# Schematic_shield_Rovables_v2.net
KiCad netlist of a schematic drawn in Altium Designer
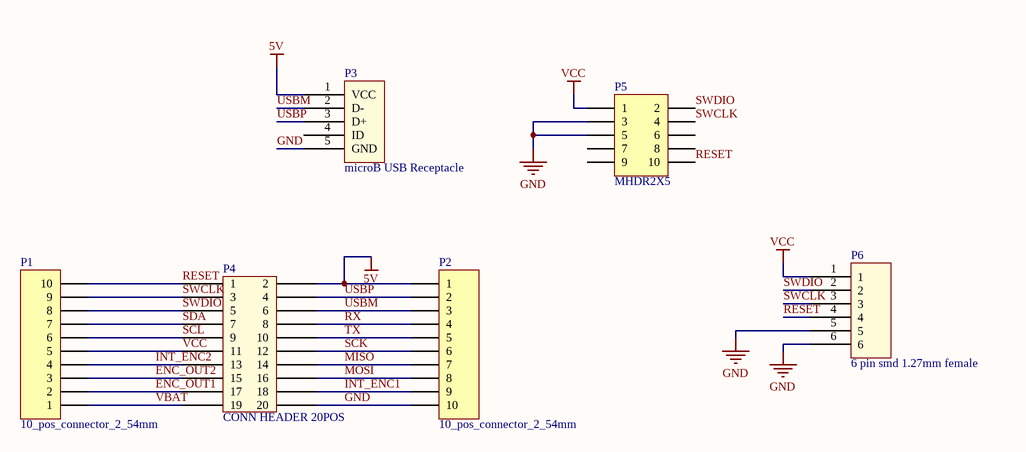
[diagram p0: Schematic_shield_Rovables_v2.SchDoc]

(export (version "E")
  (design (tool "Eeschema 10.0.6"))
  (components
    (comp (ref "P1")
      (value "10_pos_connector_2_54mm")
      (footprint "2_54mm_10_pos_connector")
      (libsource (lib "Artem_Library") (part "10_pos_connector_2_54mm"))
    )
    (comp (ref "P2")
      (value "10_pos_connector_2_54mm")
      (footprint "2_54mm_10_pos_connector")
      (libsource (lib "") (part "10_pos_connector_2_54mm_1"))
    )
    (comp (ref "P3")
      (value "microB USB Receptacle")
      (footprint "MicroB USB Standarad SMT")
      (fields (field (name "MANUFACTURER") "ZX62-B-5PA(11)"))
      (libsource (lib "Artem_Library") (part "microB USB Receptacle"))
    )
    (comp (ref "P4")
      (value "CONN HEADER 20POS")
      (footprint "DF12 20 POS")
      (fields
        (field (name "DIGIKEY PART NUMBER") "H11743CT-ND")
        (field (name "MANUFACTURER PART NUMBER") "DF12D(4.0)-20DP-0.5V(81)")
        (field (name "MANUFACTURER") "Hirose Electric Co Ltd")
      )
      (libsource (lib "Artem_Library") (part "CONN HEADER 20POS"))
    )
    (comp (ref "P5")
      (value "MHDR2X5")
      (footprint "MHDR2X5")
      (description "Header, 5-Pin, Dual row")
      (fields (field (name "PUBLISHER") "Altium Limited"))
      (libsource (lib "Miscellaneous Connectors") (part "MHDR2X5"))
    )
    (comp (ref "P6")
      (value "6 pin smd 1.27mm female")
      (footprint "6pos 1.27mm")
      (libsource (lib "Artem_Library") (part "6 pin smd 1.27mm female"))
    )
  )
  (nets
    (net (code "1") (name "/ENC_OUT1") (class "Default")
      (node (ref "P1") (pin "2") (pinfunction "2_2") (pintype "passive"))
      (node (ref "P4") (pin "17") (pinfunction "17_17") (pintype "passive"))
    )
    (net (code "2") (name "/ENC_OUT2") (class "Default")
      (node (ref "P1") (pin "3") (pinfunction "3_3") (pintype "passive"))
      (node (ref "P4") (pin "15") (pinfunction "15_15") (pintype "passive"))
    )
    (net (code "3") (name "/INT_ENC1") (class "Default")
      (node (ref "P2") (pin "9") (pinfunction "9_9") (pintype "passive"))
      (node (ref "P4") (pin "18") (pinfunction "18_18") (pintype "passive"))
    )
    (net (code "4") (name "/INT_ENC2") (class "Default")
      (node (ref "P1") (pin "4") (pinfunction "4_4") (pintype "passive"))
      (node (ref "P4") (pin "13") (pinfunction "13_13") (pintype "passive"))
    )
    (net (code "5") (name "/MISO") (class "Default")
      (node (ref "P2") (pin "7") (pinfunction "7_7") (pintype "passive"))
      (node (ref "P4") (pin "14") (pinfunction "14_14") (pintype "passive"))
    )
    (net (code "6") (name "/MOSI") (class "Default")
      (node (ref "P2") (pin "8") (pinfunction "8_8") (pintype "passive"))
      (node (ref "P4") (pin "16") (pinfunction "16_16") (pintype "passive"))
    )
    (net (code "7") (name "/RESET") (class "Default")
      (node (ref "P1") (pin "10") (pinfunction "10_10") (pintype "passive"))
      (node (ref "P4") (pin "1") (pinfunction "1_1") (pintype "passive"))
      (node (ref "P5") (pin "10") (pinfunction "10_10") (pintype "passive"))
      (node (ref "P6") (pin "4") (pinfunction "4_4") (pintype "passive"))
    )
    (net (code "8") (name "/RX") (class "Default")
      (node (ref "P2") (pin "4") (pinfunction "4_4") (pintype "passive"))
      (node (ref "P4") (pin "8") (pinfunction "8_8") (pintype "passive"))
    )
    (net (code "9") (name "/SCK") (class "Default")
      (node (ref "P2") (pin "6") (pinfunction "6_6") (pintype "passive"))
      (node (ref "P4") (pin "12") (pinfunction "12_12") (pintype "passive"))
    )
    (net (code "10") (name "/SCL") (class "Default")
      (node (ref "P1") (pin "6") (pinfunction "6_6") (pintype "passive"))
      (node (ref "P4") (pin "9") (pinfunction "9_9") (pintype "passive"))
    )
    (net (code "11") (name "/SDA") (class "Default")
      (node (ref "P1") (pin "7") (pinfunction "7_7") (pintype "passive"))
      (node (ref "P4") (pin "7") (pinfunction "7_7") (pintype "passive"))
    )
    (net (code "12") (name "/SWCLK") (class "Default")
      (node (ref "P1") (pin "9") (pinfunction "9_9") (pintype "passive"))
      (node (ref "P4") (pin "3") (pinfunction "3_3") (pintype "passive"))
      (node (ref "P5") (pin "4") (pinfunction "4_4") (pintype "passive"))
      (node (ref "P6") (pin "3") (pinfunction "3_3") (pintype "passive"))
    )
    (net (code "13") (name "/SWDIO") (class "Default")
      (node (ref "P1") (pin "8") (pinfunction "8_8") (pintype "passive"))
      (node (ref "P4") (pin "5") (pinfunction "5_5") (pintype "passive"))
      (node (ref "P5") (pin "2") (pinfunction "2_2") (pintype "passive"))
      (node (ref "P6") (pin "2") (pinfunction "2_2") (pintype "passive"))
    )
    (net (code "14") (name "/TX") (class "Default")
      (node (ref "P2") (pin "5") (pinfunction "5_5") (pintype "passive"))
      (node (ref "P4") (pin "10") (pinfunction "10_10") (pintype "passive"))
    )
    (net (code "15") (name "/USBM") (class "Default")
      (node (ref "P2") (pin "3") (pinfunction "3_3") (pintype "passive"))
      (node (ref "P3") (pin "2") (pinfunction "D-_2") (pintype "passive"))
      (node (ref "P4") (pin "6") (pinfunction "6_6") (pintype "passive"))
    )
    (net (code "16") (name "/USBP") (class "Default")
      (node (ref "P2") (pin "2") (pinfunction "2_2") (pintype "passive"))
      (node (ref "P3") (pin "3") (pinfunction "D+_3") (pintype "passive"))
      (node (ref "P4") (pin "4") (pinfunction "4_4") (pintype "passive"))
    )
    (net (code "17") (name "/VBAT") (class "Default")
      (node (ref "P1") (pin "1") (pinfunction "1_1") (pintype "passive"))
      (node (ref "P4") (pin "19") (pinfunction "19_19") (pintype "passive"))
    )
    (net (code "18") (name "5V") (class "Default")
      (node (ref "P2") (pin "1") (pinfunction "1_1") (pintype "passive"))
      (node (ref "P3") (pin "1") (pinfunction "VCC_1") (pintype "passive"))
      (node (ref "P4") (pin "2") (pinfunction "2_2") (pintype "passive"))
    )
    (net (code "19") (name "GND") (class "Default")
      (node (ref "P2") (pin "10") (pinfunction "10_10") (pintype "passive"))
      (node (ref "P3") (pin "5") (pinfunction "GND_5") (pintype "passive"))
      (node (ref "P4") (pin "20") (pinfunction "20_20") (pintype "passive"))
      (node (ref "P5") (pin "3") (pinfunction "3_3") (pintype "passive"))
      (node (ref "P5") (pin "5") (pinfunction "5_5") (pintype "passive"))
      (node (ref "P6") (pin "5") (pinfunction "5_5") (pintype "passive"))
      (node (ref "P6") (pin "6") (pinfunction "6_6") (pintype "passive"))
    )
    (net (code "20") (name "VCC") (class "Default")
      (node (ref "P1") (pin "5") (pinfunction "5_5") (pintype "passive"))
      (node (ref "P4") (pin "11") (pinfunction "11_11") (pintype "passive"))
      (node (ref "P5") (pin "1") (pinfunction "1_1") (pintype "passive"))
      (node (ref "P6") (pin "1") (pinfunction "1_1") (pintype "passive"))
    )
    (net (code "21") (name "unconnected-(P3-ID-Pad4)") (class "Default")
      (node (ref "P3") (pin "4") (pinfunction "ID_4") (pintype "passive"))
    )
    (net (code "22") (name "unconnected-(P5-Pad6)") (class "Default")
      (node (ref "P5") (pin "6") (pinfunction "6_6") (pintype "passive"))
    )
    (net (code "23") (name "unconnected-(P5-Pad7)") (class "Default")
      (node (ref "P5") (pin "7") (pinfunction "7_7") (pintype "passive"))
    )
    (net (code "24") (name "unconnected-(P5-Pad8)") (class "Default")
      (node (ref "P5") (pin "8") (pinfunction "8_8") (pintype "passive"))
    )
    (net (code "25") (name "unconnected-(P5-Pad9)") (class "Default")
      (node (ref "P5") (pin "9") (pinfunction "9_9") (pintype "passive"))
    )
  )
)
